# ProProject_Hollow-Clock-Pro_2024-01-11.net
KiCad netlist of a schematic drawn in EasyEDA Pro
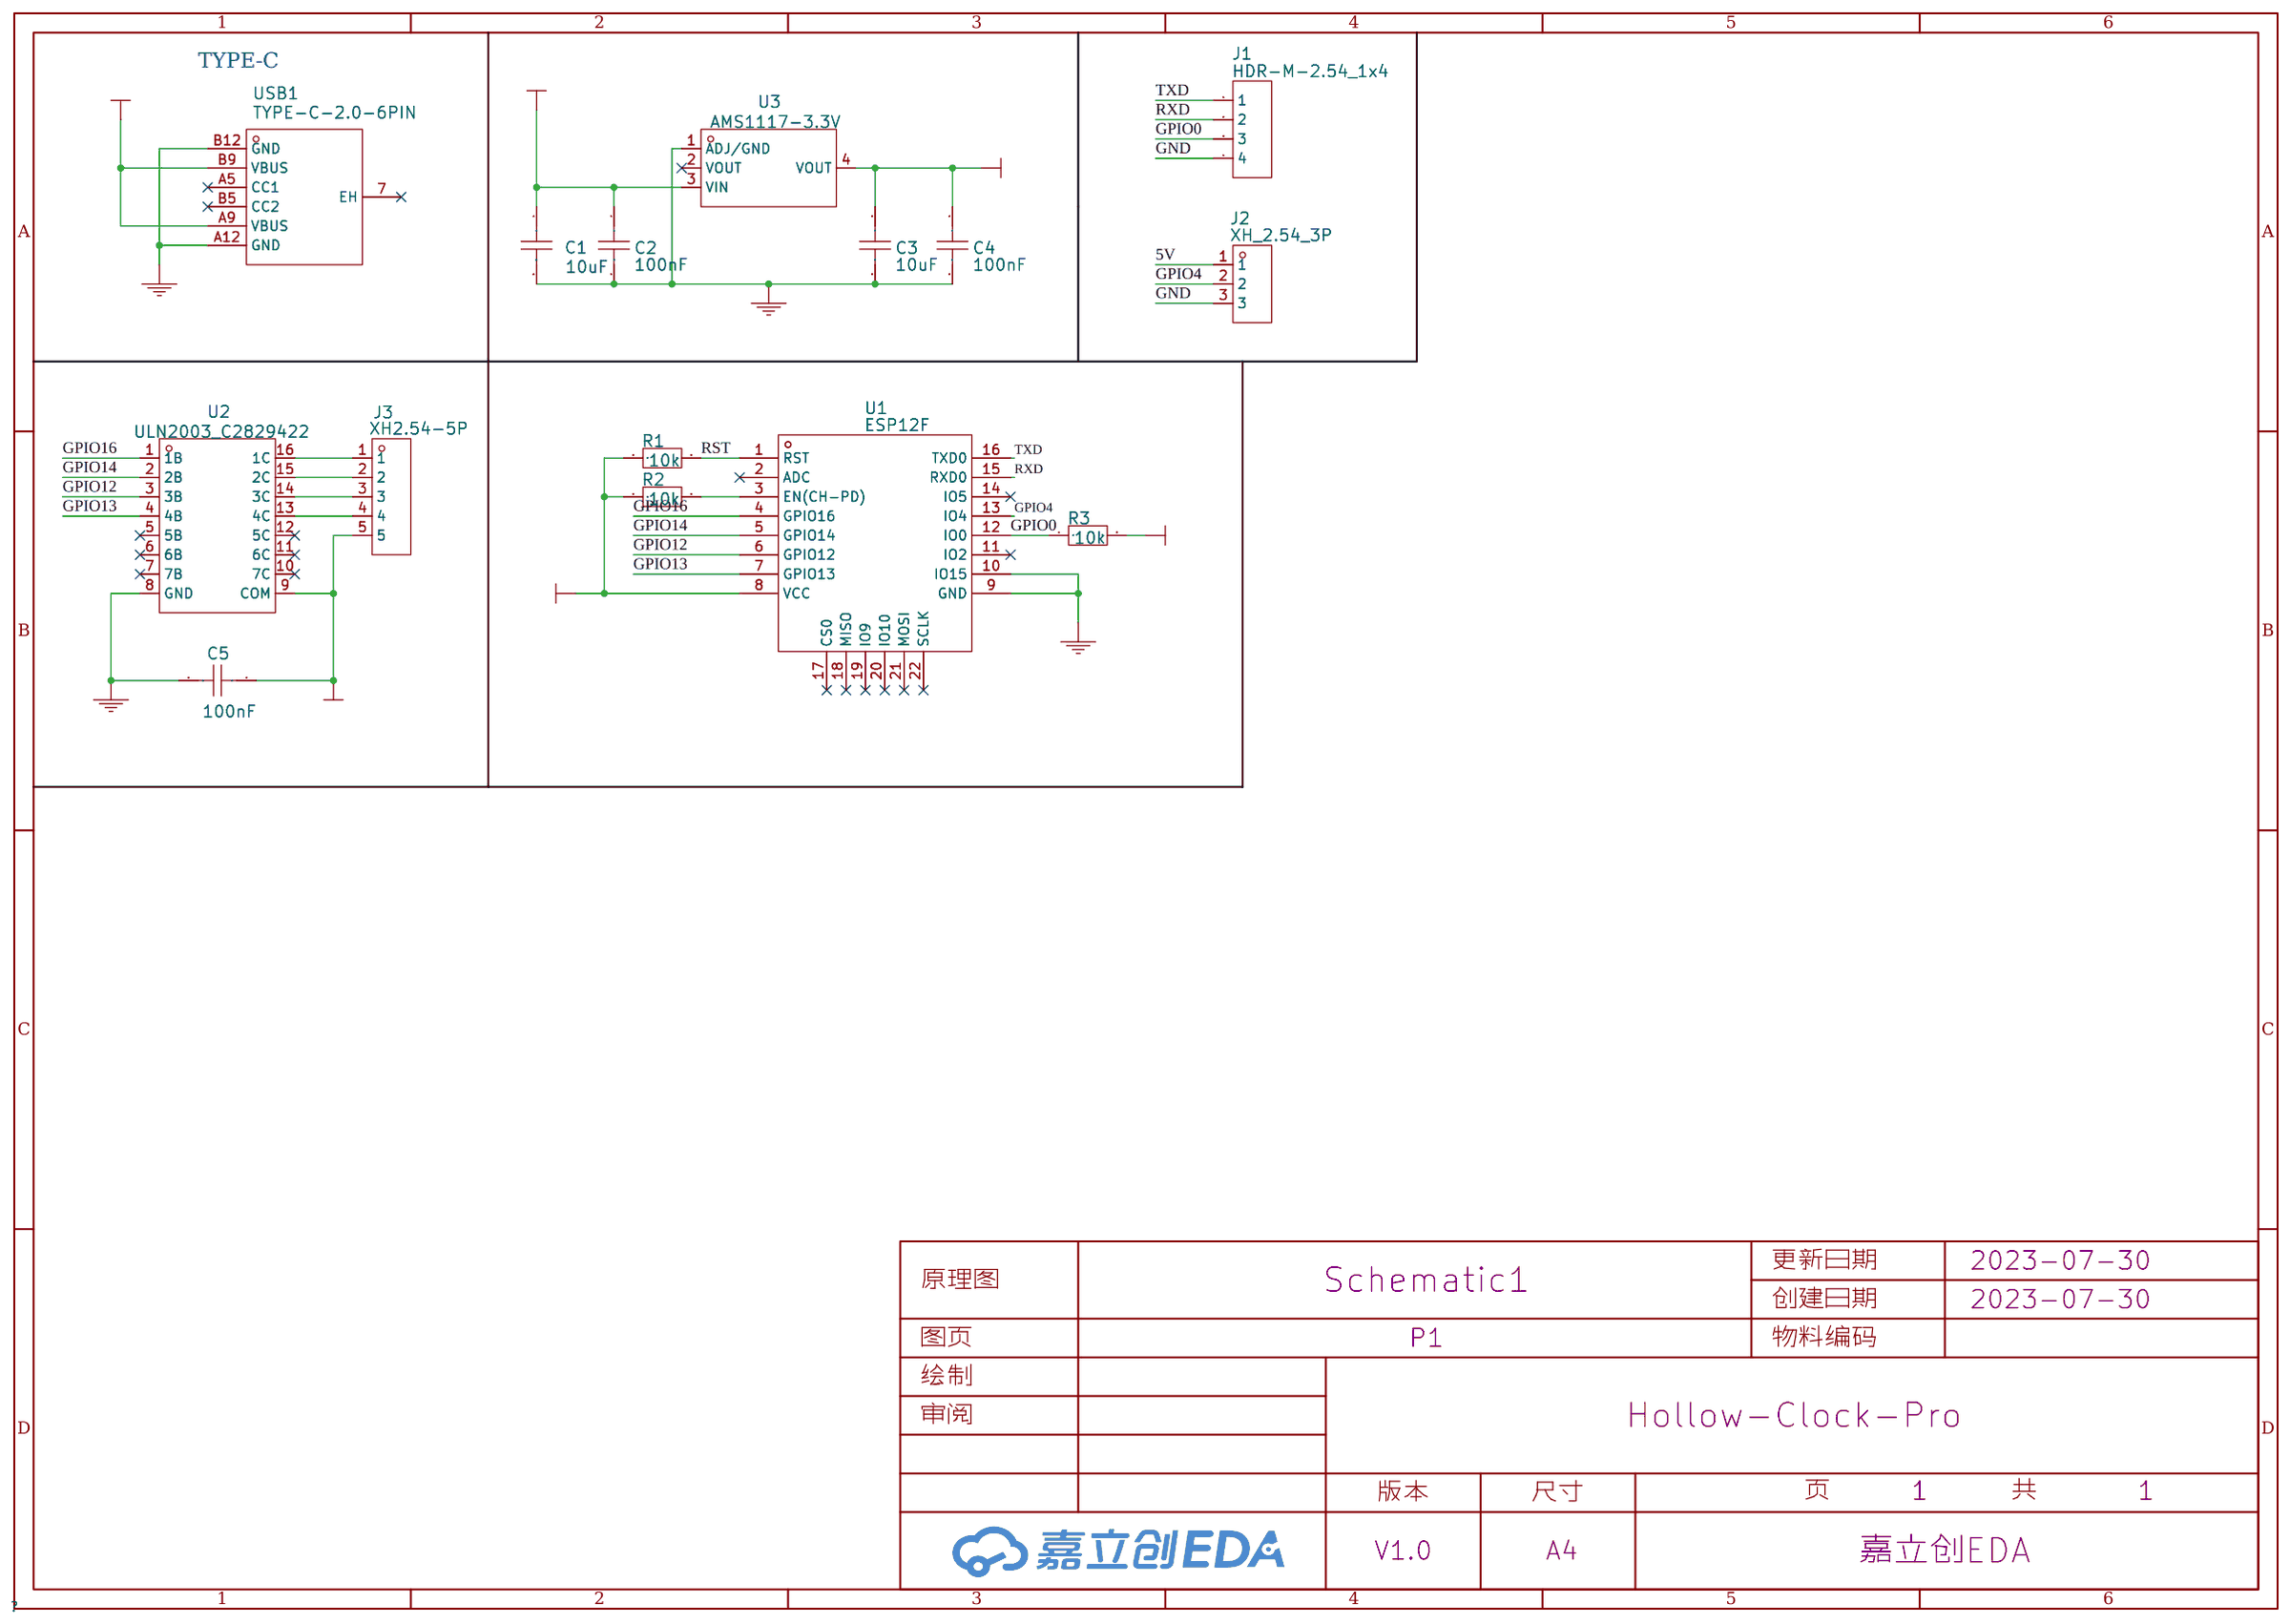
[diagram p0: schematic sheet]

(export (version "E")
  (design (tool "Eeschema 10.0.6"))
  (components
    (comp (ref "C1")
      (value "10uF")
      (footprint "easyedapro:C0603")
      (libsource (lib "easyedapro") (part "10uF"))
    )
    (comp (ref "C2")
      (value "100nF")
      (footprint "easyedapro:C0603")
      (libsource (lib "easyedapro") (part "100nF"))
    )
    (comp (ref "C3")
      (value "10uF")
      (footprint "easyedapro:C0603")
      (libsource (lib "easyedapro") (part "10uF"))
    )
    (comp (ref "C4")
      (value "100nF")
      (footprint "easyedapro:C0603")
      (libsource (lib "easyedapro") (part "100nF"))
    )
    (comp (ref "C5")
      (value "100nF")
      (footprint "easyedapro:C0603")
      (libsource (lib "easyedapro") (part "100nF"))
    )
    (comp (ref "J1")
      (value "HDR-M-2.54_1x4")
      (footprint "easyedapro:HDR-M-2.54_1X4")
      (libsource (lib "easyedapro") (part "HDR-M-2.54_1x4"))
    )
    (comp (ref "J2")
      (value "XH_2.54_3P")
      (footprint "easyedapro:CONN-TH_XH2.54-3P")
      (libsource (lib "easyedapro") (part "XH_2.54_3P"))
    )
    (comp (ref "J3")
      (value "XH2.54-5P")
      (footprint "easyedapro:CONN-TH_XH2.54-5P")
      (fields (field (name "Manufacturer Part") "XH2.54-5P 直插"))
      (libsource (lib "easyedapro") (part "XH2.54-5P"))
    )
    (comp (ref "R1") (value "10k") (footprint "easyedapro:R0603") (libsource (lib "easyedapro") (part "10k")))
    (comp (ref "R2") (value "10k") (footprint "easyedapro:R0603") (libsource (lib "easyedapro") (part "10k")))
    (comp (ref "R3") (value "10k") (footprint "easyedapro:R0603") (libsource (lib "easyedapro") (part "10k")))
    (comp (ref "U1")
      (value "ESP12F")
      (footprint "easyedapro:ESP12F/S")
      (libsource (lib "easyedapro") (part "ESP12F"))
    )
    (comp (ref "U2")
      (value "ULN2003_C2829422")
      (footprint "easyedapro:SOP-16_L9.9-W3.9-P1.27-LS6.0-BL")
      (fields (field (name "Manufacturer Part") "ULN2003") (field (name "Manufacturer") "CJ(江苏长电/长晶)"))
      (libsource (lib "easyedapro") (part "ULN2003_C2829422"))
    )
    (comp (ref "U3")
      (value "AMS1117-3.3V")
      (footprint "easyedapro:SOT-223-4_L6.5-W3.5-P2.30-LS7.0-BR")
      (fields (field (name "Manufacturer") "WPMtek(维攀微)"))
      (libsource (lib "easyedapro") (part "AMS1117-3.3V"))
    )
    (comp (ref "USB1")
      (value "TYPE-C-2.0-6PIN")
      (footprint "easyedapro:TYPE-C-SMD_TYPE-C-6P-2")
      (fields (field (name "Manufacturer Part") "Type-C-2.0-6Pin") (field (name "Manufacturer") "CIKI(皓富)"))
      (libsource (lib "easyedapro") (part "TYPE-C-2.0-6PIN"))
    )
  )
  (nets
    (net (code "1") (name "/GPIO0") (class "Default")
      (node (ref "J1") (pin "3") (pinfunction "3_3") (pintype "input"))
      (node (ref "R3") (pin "1") (pinfunction "1_1") (pintype "input"))
      (node (ref "U1") (pin "12") (pinfunction "IO0_12") (pintype "input"))
    )
    (net (code "2") (name "/GPIO4") (class "Default")
      (node (ref "J2") (pin "2") (pinfunction "2_2") (pintype "input"))
      (node (ref "U1") (pin "13") (pinfunction "IO4_13") (pintype "input"))
    )
    (net (code "3") (name "/GPIO12") (class "Default")
      (node (ref "U1") (pin "6") (pinfunction "GPIO12_6") (pintype "input"))
      (node (ref "U2") (pin "3") (pinfunction "3B_3") (pintype "input"))
    )
    (net (code "4") (name "/GPIO13") (class "Default")
      (node (ref "U1") (pin "7") (pinfunction "GPIO13_7") (pintype "input"))
      (node (ref "U2") (pin "4") (pinfunction "4B_4") (pintype "input"))
    )
    (net (code "5") (name "/GPIO14") (class "Default")
      (node (ref "U1") (pin "5") (pinfunction "GPIO14_5") (pintype "input"))
      (node (ref "U2") (pin "2") (pinfunction "2B_2") (pintype "input"))
    )
    (net (code "6") (name "/GPIO16") (class "Default")
      (node (ref "U1") (pin "4") (pinfunction "GPIO16_4") (pintype "input"))
      (node (ref "U2") (pin "1") (pinfunction "1B_1") (pintype "input"))
    )
    (net (code "7") (name "/RST") (class "Default")
      (node (ref "R1") (pin "2") (pinfunction "2_2") (pintype "input"))
      (node (ref "U1") (pin "1") (pinfunction "RST_1") (pintype "input"))
    )
    (net (code "8") (name "/RXD") (class "Default")
      (node (ref "J1") (pin "2") (pinfunction "2_2") (pintype "input"))
      (node (ref "U1") (pin "15") (pinfunction "RXD0_15") (pintype "input"))
    )
    (net (code "9") (name "/TXD") (class "Default")
      (node (ref "J1") (pin "1") (pinfunction "1_1") (pintype "input"))
      (node (ref "U1") (pin "16") (pinfunction "TXD0_16") (pintype "input"))
    )
    (net (code "10") (name "3.3V") (class "Default")
      (node (ref "C3") (pin "1") (pinfunction "1_1") (pintype "input"))
      (node (ref "C4") (pin "1") (pinfunction "1_1") (pintype "input"))
      (node (ref "R1") (pin "1") (pinfunction "1_1") (pintype "input"))
      (node (ref "R2") (pin "1") (pinfunction "1_1") (pintype "input"))
      (node (ref "R3") (pin "2") (pinfunction "2_2") (pintype "input"))
      (node (ref "U1") (pin "8") (pinfunction "VCC_8") (pintype "input"))
      (node (ref "U3") (pin "4") (pinfunction "VOUT_4") (pintype "input"))
    )
    (net (code "11") (name "5V") (class "Default")
      (node (ref "C1") (pin "1") (pinfunction "1_1") (pintype "input"))
      (node (ref "C2") (pin "1") (pinfunction "1_1") (pintype "input"))
      (node (ref "C5") (pin "1") (pinfunction "1_1") (pintype "input"))
      (node (ref "J2") (pin "1") (pinfunction "1_1") (pintype "input"))
      (node (ref "J3") (pin "5") (pinfunction "5_5") (pintype "input"))
      (node (ref "U2") (pin "9") (pinfunction "COM_9") (pintype "input"))
      (node (ref "U3") (pin "3") (pinfunction "VIN_3") (pintype "input"))
      (node (ref "USB1") (pin "A9") (pinfunction "VBUS_A9") (pintype "input"))
      (node (ref "USB1") (pin "B9") (pinfunction "VBUS_B9") (pintype "input"))
    )
    (net (code "12") (name "GND") (class "Default")
      (node (ref "C1") (pin "2") (pinfunction "2_2") (pintype "input"))
      (node (ref "C2") (pin "2") (pinfunction "2_2") (pintype "input"))
      (node (ref "C3") (pin "2") (pinfunction "2_2") (pintype "input"))
      (node (ref "C4") (pin "2") (pinfunction "2_2") (pintype "input"))
      (node (ref "C5") (pin "2") (pinfunction "2_2") (pintype "input"))
      (node (ref "J1") (pin "4") (pinfunction "4_4") (pintype "input"))
      (node (ref "J2") (pin "3") (pinfunction "3_3") (pintype "input"))
      (node (ref "U1") (pin "10") (pinfunction "IO15_10") (pintype "input"))
      (node (ref "U1") (pin "9") (pinfunction "GND_9") (pintype "input"))
      (node (ref "U2") (pin "8") (pinfunction "GND_8") (pintype "input"))
      (node (ref "U3") (pin "1") (pinfunction "ADJ/GND_1") (pintype "input"))
      (node (ref "USB1") (pin "A12") (pinfunction "GND_A12") (pintype "input"))
      (node (ref "USB1") (pin "B12") (pinfunction "GND_B12") (pintype "input"))
    )
    (net (code "13") (name "Net-(U1-EN(CH-PD))") (class "Default")
      (node (ref "R2") (pin "2") (pinfunction "2_2") (pintype "input"))
      (node (ref "U1") (pin "3") (pinfunction "EN(CH-PD)_3") (pintype "input"))
    )
    (net (code "14") (name "Net-(U2-1C)") (class "Default")
      (node (ref "J3") (pin "1") (pinfunction "1_1") (pintype "input"))
      (node (ref "U2") (pin "16") (pinfunction "1C_16") (pintype "input"))
    )
    (net (code "15") (name "Net-(U2-2C)") (class "Default")
      (node (ref "J3") (pin "2") (pinfunction "2_2") (pintype "input"))
      (node (ref "U2") (pin "15") (pinfunction "2C_15") (pintype "input"))
    )
    (net (code "16") (name "Net-(U2-3C)") (class "Default")
      (node (ref "J3") (pin "3") (pinfunction "3_3") (pintype "input"))
      (node (ref "U2") (pin "14") (pinfunction "3C_14") (pintype "input"))
    )
    (net (code "17") (name "Net-(U2-4C)") (class "Default")
      (node (ref "J3") (pin "4") (pinfunction "4_4") (pintype "input"))
      (node (ref "U2") (pin "13") (pinfunction "4C_13") (pintype "input"))
    )
    (net (code "18") (name "unconnected-(U1-ADC-Pad2)") (class "Default")
      (node (ref "U1") (pin "2") (pinfunction "ADC_2") (pintype "input+no_connect"))
    )
    (net (code "19") (name "unconnected-(U1-CS0-Pad17)") (class "Default")
      (node (ref "U1") (pin "17") (pinfunction "CS0_17") (pintype "input+no_connect"))
    )
    (net (code "20") (name "unconnected-(U1-IO2-Pad11)") (class "Default")
      (node (ref "U1") (pin "11") (pinfunction "IO2_11") (pintype "input+no_connect"))
    )
    (net (code "21") (name "unconnected-(U1-IO5-Pad14)") (class "Default")
      (node (ref "U1") (pin "14") (pinfunction "IO5_14") (pintype "input+no_connect"))
    )
    (net (code "22") (name "unconnected-(U1-IO9-Pad19)") (class "Default")
      (node (ref "U1") (pin "19") (pinfunction "IO9_19") (pintype "input+no_connect"))
    )
    (net (code "23") (name "unconnected-(U1-IO10-Pad20)") (class "Default")
      (node (ref "U1") (pin "20") (pinfunction "IO10_20") (pintype "input+no_connect"))
    )
    (net (code "24") (name "unconnected-(U1-MISO-Pad18)") (class "Default")
      (node (ref "U1") (pin "18") (pinfunction "MISO_18") (pintype "input+no_connect"))
    )
    (net (code "25") (name "unconnected-(U1-MOSI-Pad21)") (class "Default")
      (node (ref "U1") (pin "21") (pinfunction "MOSI_21") (pintype "input+no_connect"))
    )
    (net (code "26") (name "unconnected-(U1-SCLK-Pad22)") (class "Default")
      (node (ref "U1") (pin "22") (pinfunction "SCLK_22") (pintype "input+no_connect"))
    )
    (net (code "27") (name "unconnected-(U2-5B-Pad5)") (class "Default")
      (node (ref "U2") (pin "5") (pinfunction "5B_5") (pintype "input+no_connect"))
    )
    (net (code "28") (name "unconnected-(U2-5C-Pad12)") (class "Default")
      (node (ref "U2") (pin "12") (pinfunction "5C_12") (pintype "input+no_connect"))
    )
    (net (code "29") (name "unconnected-(U2-6B-Pad6)") (class "Default")
      (node (ref "U2") (pin "6") (pinfunction "6B_6") (pintype "input+no_connect"))
    )
    (net (code "30") (name "unconnected-(U2-6C-Pad11)") (class "Default")
      (node (ref "U2") (pin "11") (pinfunction "6C_11") (pintype "input+no_connect"))
    )
    (net (code "31") (name "unconnected-(U2-7B-Pad7)") (class "Default")
      (node (ref "U2") (pin "7") (pinfunction "7B_7") (pintype "input+no_connect"))
    )
    (net (code "32") (name "unconnected-(U2-7C-Pad10)") (class "Default")
      (node (ref "U2") (pin "10") (pinfunction "7C_10") (pintype "input+no_connect"))
    )
    (net (code "33") (name "unconnected-(U3-VOUT-Pad2)") (class "Default")
      (node (ref "U3") (pin "2") (pinfunction "VOUT_2") (pintype "input+no_connect"))
    )
    (net (code "34") (name "unconnected-(USB1-CC1-PadA5)") (class "Default")
      (node (ref "USB1") (pin "A5") (pinfunction "CC1_A5") (pintype "input+no_connect"))
    )
    (net (code "35") (name "unconnected-(USB1-CC2-PadB5)") (class "Default")
      (node (ref "USB1") (pin "B5") (pinfunction "CC2_B5") (pintype "input+no_connect"))
    )
    (net (code "36") (name "unconnected-(USB1-EH-Pad7)") (class "Default")
      (node (ref "USB1") (pin "7") (pinfunction "EH_7") (pintype "input+no_connect"))
    )
  )
)
